# receiver.net
KiCad netlist of a schematic drawn in EAGLE
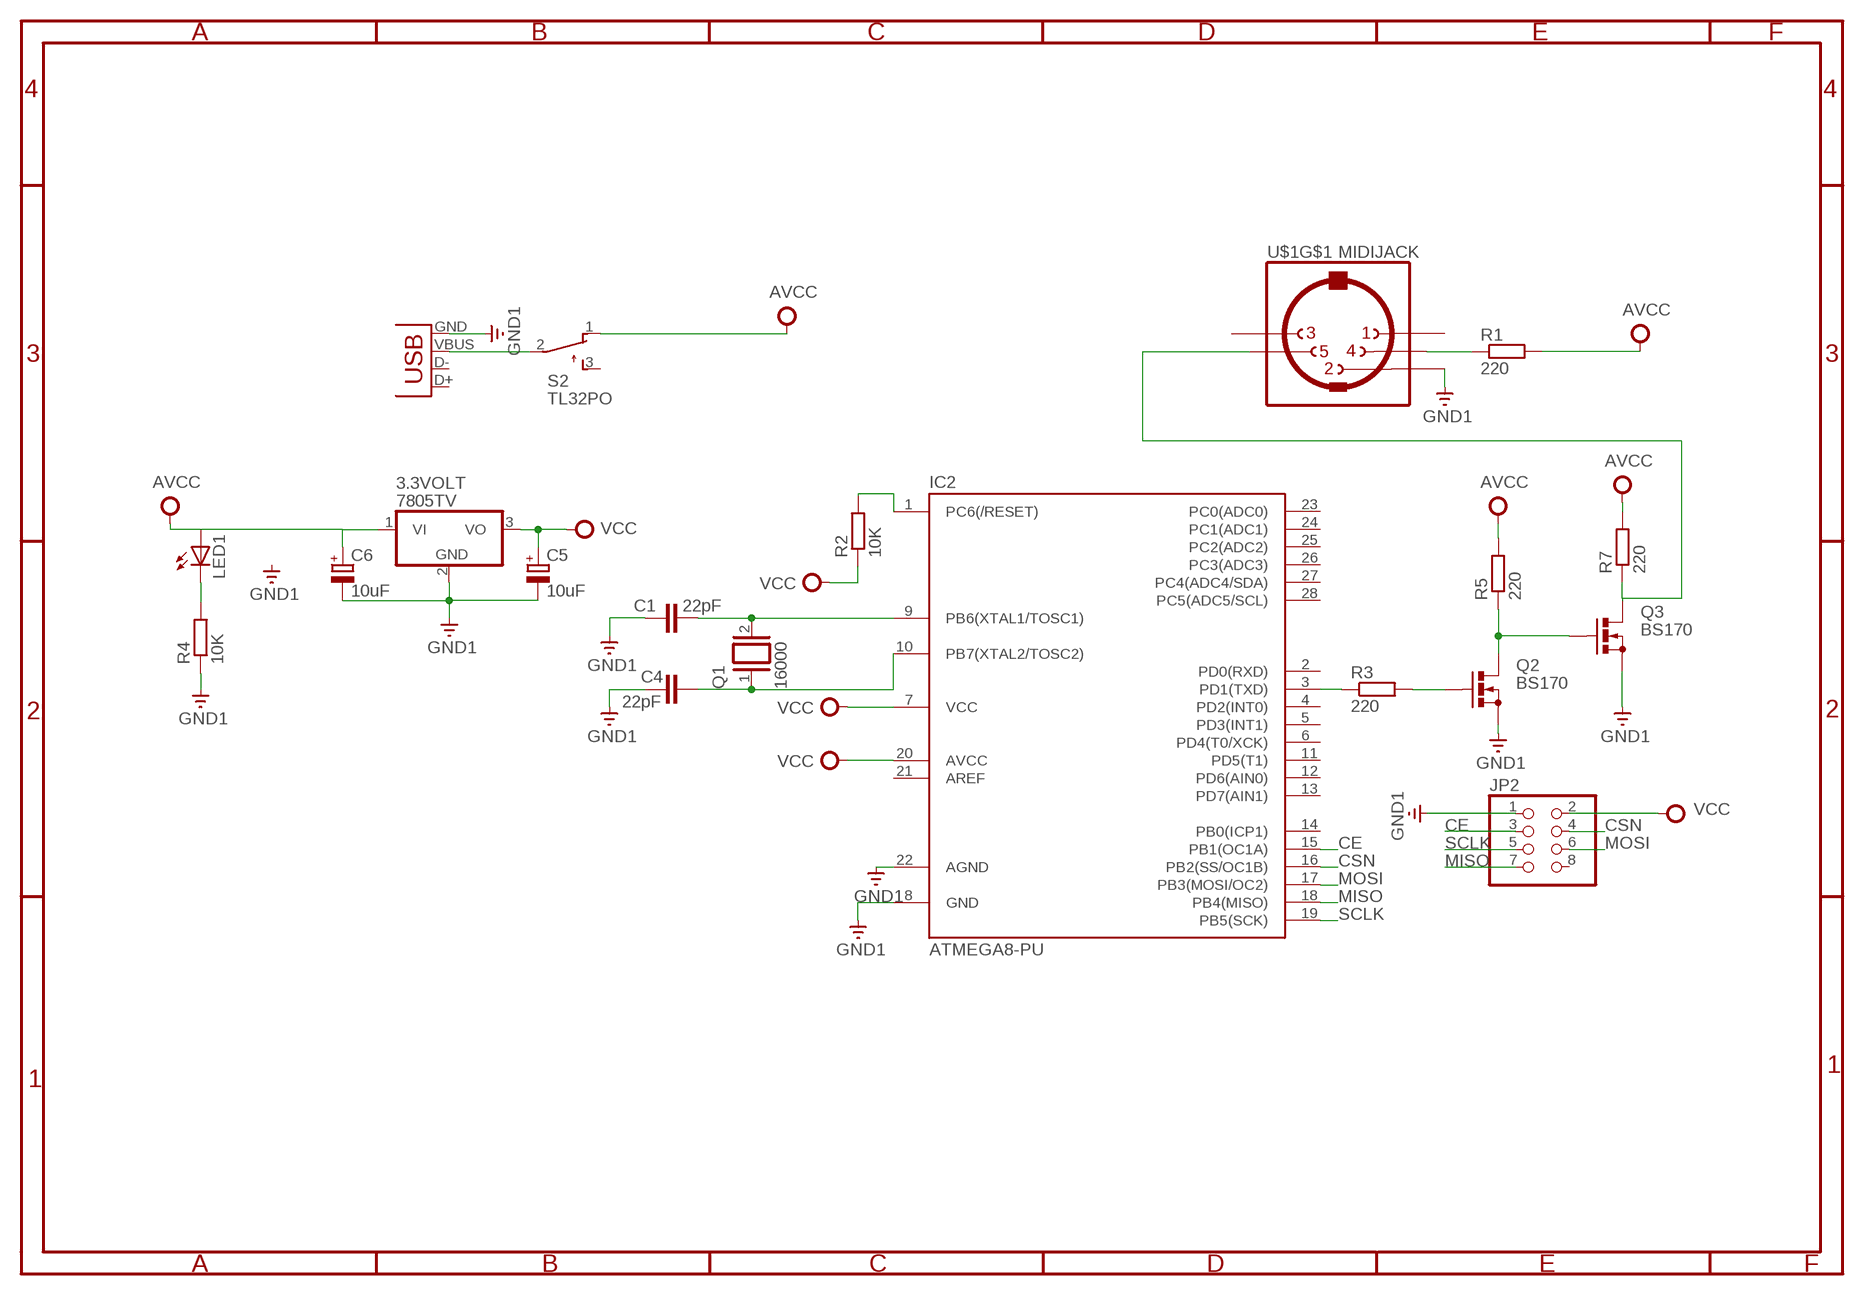
[diagram p0: schematic, sheet 1]

(export (version "E")
  (design (tool "Eeschema 10.0.6"))
  (components
    (comp (ref "3.3VOLT")
      (value "7805TV")
      (footprint "eagle-import:TO220V")
      (libsource (lib "eagle-import") (part "78TV05"))
    )
    (comp (ref "C1")
      (value "22pF")
      (footprint "eagle-import:C050-025X075")
      (libsource (lib "eagle-import") (part "C-EU050-025X075"))
    )
    (comp (ref "C4")
      (value "22pF")
      (footprint "eagle-import:C050-025X075")
      (libsource (lib "eagle-import") (part "C-EU050-025X075"))
    )
    (comp (ref "C5")
      (value "10uF")
      (footprint "eagle-import:E2,5-5")
      (libsource (lib "eagle-import") (part "CPOL-EUE2.5-5"))
    )
    (comp (ref "C6")
      (value "10uF")
      (footprint "eagle-import:E2,5-5")
      (libsource (lib "eagle-import") (part "CPOL-EUE2.5-5"))
    )
    (comp (ref "IC2")
      (value "ATMEGA8-PU")
      (footprint "eagle-import:DIL28-3")
      (libsource (lib "eagle-import") (part "ATMEGA8-PU"))
    )
    (comp (ref "JP2")
      (value "PINHD-2X4")
      (footprint "eagle-import:2X04")
      (libsource (lib "eagle-import") (part "PINHD-2X4"))
    )
    (comp (ref "LED1")
      (value "LED5MM")
      (footprint "eagle-import:LED5MM")
      (libsource (lib "eagle-import") (part "LED5MM"))
    )
    (comp (ref "Q1")
      (value "16000")
      (footprint "eagle-import:QS")
      (libsource (lib "eagle-import") (part "XTAL/S"))
    )
    (comp (ref "Q2")
      (value "BS170")
      (footprint "eagle-import:SOT54E")
      (libsource (lib "eagle-import") (part "BS170"))
    )
    (comp (ref "Q3")
      (value "BS170")
      (footprint "eagle-import:SOT54E")
      (libsource (lib "eagle-import") (part "BS170"))
    )
    (comp (ref "R1")
      (value "220")
      (footprint "eagle-import:0204_7")
      (libsource (lib "eagle-import") (part "R0204/7"))
    )
    (comp (ref "R2")
      (value "10K")
      (footprint "eagle-import:0204_7")
      (libsource (lib "eagle-import") (part "R0204/7"))
    )
    (comp (ref "R3")
      (value "220")
      (footprint "eagle-import:0204_7")
      (libsource (lib "eagle-import") (part "R0204/7"))
    )
    (comp (ref "R4")
      (value "10K")
      (footprint "eagle-import:0204_7")
      (libsource (lib "eagle-import") (part "R0204/7"))
    )
    (comp (ref "R5")
      (value "220")
      (footprint "eagle-import:0204_7")
      (libsource (lib "eagle-import") (part "R0204/7"))
    )
    (comp (ref "R7")
      (value "220")
      (footprint "eagle-import:0204_7")
      (libsource (lib "eagle-import") (part "R0204/7"))
    )
    (comp (ref "S2")
      (value "TL32PO")
      (footprint "eagle-import:TL3XPO")
      (libsource (lib "eagle-import") (part "TL32PO"))
    )
    (comp (ref "U$1")
      (value "MIDIJACK")
      (footprint "eagle-import:CP-2350")
      (libsource (lib "eagle-import") (part "MIDIJACK"))
    )
    (comp (ref "X1")
      (value "USB-B-H")
      (footprint "eagle-import:USB-B-H")
      (libsource (lib "eagle-import") (part "USB-B-H"))
    )
  )
  (nets
    (net (code "1") (name "/CE") (class "Default")
      (node (ref "IC2") (pin "15") (pinfunction "PB1(OC1A)_15") (pintype "bidirectional"))
      (node (ref "JP2") (pin "3") (pinfunction "3_3") (pintype "passive"))
    )
    (net (code "2") (name "/CSN") (class "Default")
      (node (ref "IC2") (pin "16") (pinfunction "PB2(SS/OC1B)_16") (pintype "bidirectional"))
      (node (ref "JP2") (pin "4") (pinfunction "4_4") (pintype "passive"))
    )
    (net (code "3") (name "/MISO") (class "Default")
      (node (ref "IC2") (pin "18") (pinfunction "PB4(MISO)_18") (pintype "bidirectional"))
      (node (ref "JP2") (pin "7") (pinfunction "7_7") (pintype "passive"))
    )
    (net (code "4") (name "/MOSI") (class "Default")
      (node (ref "IC2") (pin "17") (pinfunction "PB3(MOSI/OC2)_17") (pintype "bidirectional"))
      (node (ref "JP2") (pin "6") (pinfunction "6_6") (pintype "passive"))
    )
    (net (code "5") (name "/SCLK") (class "Default")
      (node (ref "IC2") (pin "19") (pinfunction "PB5(SCK)_19") (pintype "bidirectional"))
      (node (ref "JP2") (pin "5") (pinfunction "5_5") (pintype "passive"))
    )
    (net (code "6") (name "AVCC") (class "Default")
      (node (ref "3.3VOLT") (pin "1") (pinfunction "VI_1") (pintype "input"))
      (node (ref "C6") (pin "+") (pinfunction "+_+") (pintype "passive"))
      (node (ref "LED1") (pin "A") (pinfunction "A_A") (pintype "passive"))
      (node (ref "R1") (pin "2") (pinfunction "2_2") (pintype "passive"))
      (node (ref "R5") (pin "2") (pinfunction "2_2") (pintype "passive"))
      (node (ref "R7") (pin "2") (pinfunction "2_2") (pintype "passive"))
      (node (ref "S2") (pin "1") (pinfunction "O_1") (pintype "passive"))
    )
    (net (code "7") (name "GND1") (class "Default")
      (node (ref "3.3VOLT") (pin "2") (pinfunction "GND_2") (pintype "passive"))
      (node (ref "C1") (pin "1") (pinfunction "1_1") (pintype "passive"))
      (node (ref "C4") (pin "1") (pinfunction "1_1") (pintype "passive"))
      (node (ref "C5") (pin "-") (pinfunction "-_-") (pintype "passive"))
      (node (ref "C6") (pin "-") (pinfunction "-_-") (pintype "passive"))
      (node (ref "IC2") (pin "22") (pinfunction "AGND_22") (pintype "power_in"))
      (node (ref "IC2") (pin "8") (pinfunction "GND_8") (pintype "power_in"))
      (node (ref "JP2") (pin "1") (pinfunction "1_1") (pintype "passive"))
      (node (ref "Q2") (pin "S") (pinfunction "S_S") (pintype "passive"))
      (node (ref "Q3") (pin "S") (pinfunction "S_S") (pintype "passive"))
      (node (ref "R4") (pin "1") (pinfunction "1_1") (pintype "passive"))
      (node (ref "U$1") (pin "2") (pinfunction "2_2") (pintype "passive"))
      (node (ref "X1") (pin "GND") (pinfunction "GND_GND") (pintype "bidirectional"))
    )
    (net (code "8") (name "Net-(IC2-PB6(XTAL1{slash}TOSC1))") (class "Default")
      (node (ref "C1") (pin "2") (pinfunction "2_2") (pintype "passive"))
      (node (ref "IC2") (pin "9") (pinfunction "PB6(XTAL1/TOSC1)_9") (pintype "bidirectional"))
      (node (ref "Q1") (pin "2") (pinfunction "2_2") (pintype "passive"))
    )
    (net (code "9") (name "Net-(IC2-PB7(XTAL2{slash}TOSC2))") (class "Default")
      (node (ref "C4") (pin "2") (pinfunction "2_2") (pintype "passive"))
      (node (ref "IC2") (pin "10") (pinfunction "PB7(XTAL2/TOSC2)_10") (pintype "bidirectional"))
      (node (ref "Q1") (pin "1") (pinfunction "1_1") (pintype "passive"))
    )
    (net (code "10") (name "Net-(IC2-PC6({slash}RESET))") (class "Default")
      (node (ref "IC2") (pin "1") (pinfunction "PC6(/RESET)_1") (pintype "bidirectional"))
      (node (ref "R2") (pin "2") (pinfunction "2_2") (pintype "passive"))
    )
    (net (code "11") (name "Net-(IC2-PD1(TXD))") (class "Default")
      (node (ref "IC2") (pin "3") (pinfunction "PD1(TXD)_3") (pintype "bidirectional"))
      (node (ref "R3") (pin "1") (pinfunction "1_1") (pintype "passive"))
    )
    (net (code "12") (name "Net-(LED1-C)") (class "Default")
      (node (ref "LED1") (pin "K") (pinfunction "C_K") (pintype "passive"))
      (node (ref "R4") (pin "2") (pinfunction "2_2") (pintype "passive"))
    )
    (net (code "13") (name "Net-(Q2-PadD)") (class "Default")
      (node (ref "Q2") (pin "D") (pinfunction "D_D") (pintype "passive"))
      (node (ref "Q3") (pin "G") (pinfunction "G_G") (pintype "passive"))
      (node (ref "R5") (pin "1") (pinfunction "1_1") (pintype "passive"))
    )
    (net (code "14") (name "Net-(Q2-PadG)") (class "Default")
      (node (ref "Q2") (pin "G") (pinfunction "G_G") (pintype "passive"))
      (node (ref "R3") (pin "2") (pinfunction "2_2") (pintype "passive"))
    )
    (net (code "15") (name "Net-(Q3-PadD)") (class "Default")
      (node (ref "Q3") (pin "D") (pinfunction "D_D") (pintype "passive"))
      (node (ref "R7") (pin "1") (pinfunction "1_1") (pintype "passive"))
      (node (ref "U$1") (pin "5") (pinfunction "5_5") (pintype "passive"))
    )
    (net (code "16") (name "Net-(R1-Pad1)") (class "Default")
      (node (ref "R1") (pin "1") (pinfunction "1_1") (pintype "passive"))
      (node (ref "U$1") (pin "4") (pinfunction "4_4") (pintype "passive"))
    )
    (net (code "17") (name "Net-(S2-P)") (class "Default")
      (node (ref "S2") (pin "2") (pinfunction "P_2") (pintype "passive"))
      (node (ref "X1") (pin "VBUS") (pinfunction "VBUS_VBUS") (pintype "bidirectional"))
    )
    (net (code "18") (name "VCC") (class "Default")
      (node (ref "3.3VOLT") (pin "3") (pinfunction "VO_3") (pintype "passive"))
      (node (ref "C5") (pin "+") (pinfunction "+_+") (pintype "passive"))
      (node (ref "IC2") (pin "20") (pinfunction "AVCC_20") (pintype "passive"))
      (node (ref "IC2") (pin "7") (pinfunction "VCC_7") (pintype "power_in"))
      (node (ref "JP2") (pin "2") (pinfunction "2_2") (pintype "passive"))
      (node (ref "R2") (pin "1") (pinfunction "1_1") (pintype "passive"))
    )
    (net (code "19") (name "unconnected-(IC2-AREF-Pad21)") (class "Default")
      (node (ref "IC2") (pin "21") (pinfunction "AREF_21") (pintype "passive"))
    )
    (net (code "20") (name "unconnected-(IC2-PB0(ICP1)-Pad14)") (class "Default")
      (node (ref "IC2") (pin "14") (pinfunction "PB0(ICP1)_14") (pintype "bidirectional"))
    )
    (net (code "21") (name "unconnected-(IC2-PC0(ADC0)-Pad23)") (class "Default")
      (node (ref "IC2") (pin "23") (pinfunction "PC0(ADC0)_23") (pintype "bidirectional"))
    )
    (net (code "22") (name "unconnected-(IC2-PC1(ADC1)-Pad24)") (class "Default")
      (node (ref "IC2") (pin "24") (pinfunction "PC1(ADC1)_24") (pintype "bidirectional"))
    )
    (net (code "23") (name "unconnected-(IC2-PC2(ADC2)-Pad25)") (class "Default")
      (node (ref "IC2") (pin "25") (pinfunction "PC2(ADC2)_25") (pintype "bidirectional"))
    )
    (net (code "24") (name "unconnected-(IC2-PC3(ADC3)-Pad26)") (class "Default")
      (node (ref "IC2") (pin "26") (pinfunction "PC3(ADC3)_26") (pintype "bidirectional"))
    )
    (net (code "25") (name "unconnected-(IC2-PC4(ADC4{slash}SDA)-Pad27)") (class "Default")
      (node (ref "IC2") (pin "27") (pinfunction "PC4(ADC4/SDA)_27") (pintype "bidirectional"))
    )
    (net (code "26") (name "unconnected-(IC2-PC5(ADC5{slash}SCL)-Pad28)") (class "Default")
      (node (ref "IC2") (pin "28") (pinfunction "PC5(ADC5/SCL)_28") (pintype "bidirectional"))
    )
    (net (code "27") (name "unconnected-(IC2-PD0(RXD)-Pad2)") (class "Default")
      (node (ref "IC2") (pin "2") (pinfunction "PD0(RXD)_2") (pintype "bidirectional"))
    )
    (net (code "28") (name "unconnected-(IC2-PD2(INT0)-Pad4)") (class "Default")
      (node (ref "IC2") (pin "4") (pinfunction "PD2(INT0)_4") (pintype "bidirectional"))
    )
    (net (code "29") (name "unconnected-(IC2-PD3(INT1)-Pad5)") (class "Default")
      (node (ref "IC2") (pin "5") (pinfunction "PD3(INT1)_5") (pintype "bidirectional"))
    )
    (net (code "30") (name "unconnected-(IC2-PD4(T0{slash}XCK)-Pad6)") (class "Default")
      (node (ref "IC2") (pin "6") (pinfunction "PD4(T0/XCK)_6") (pintype "bidirectional"))
    )
    (net (code "31") (name "unconnected-(IC2-PD5(T1)-Pad11)") (class "Default")
      (node (ref "IC2") (pin "11") (pinfunction "PD5(T1)_11") (pintype "bidirectional"))
    )
    (net (code "32") (name "unconnected-(IC2-PD6(AIN0)-Pad12)") (class "Default")
      (node (ref "IC2") (pin "12") (pinfunction "PD6(AIN0)_12") (pintype "bidirectional"))
    )
    (net (code "33") (name "unconnected-(IC2-PD7(AIN1)-Pad13)") (class "Default")
      (node (ref "IC2") (pin "13") (pinfunction "PD7(AIN1)_13") (pintype "bidirectional"))
    )
    (net (code "34") (name "unconnected-(JP2-Pad8)") (class "Default")
      (node (ref "JP2") (pin "8") (pinfunction "8_8") (pintype "passive"))
    )
    (net (code "35") (name "unconnected-(S2-S-Pad3)") (class "Default")
      (node (ref "S2") (pin "3") (pinfunction "S_3") (pintype "passive"))
    )
    (net (code "36") (name "unconnected-(U$1-Pad1)") (class "Default")
      (node (ref "U$1") (pin "1") (pinfunction "1_1") (pintype "passive"))
    )
    (net (code "37") (name "unconnected-(U$1-Pad3)") (class "Default")
      (node (ref "U$1") (pin "3") (pinfunction "3_3") (pintype "passive"))
    )
    (net (code "38") (name "unconnected-(X1-PadD+)") (class "Default")
      (node (ref "X1") (pin "D+") (pinfunction "D+_D+") (pintype "bidirectional"))
    )
    (net (code "39") (name "unconnected-(X1-PadD-)") (class "Default")
      (node (ref "X1") (pin "D-") (pinfunction "D-_D-") (pintype "bidirectional"))
    )
  )
)
